# 16_Vibrationsdriver_PCA9685_1.net
KiCad netlist of a schematic drawn in EAGLE
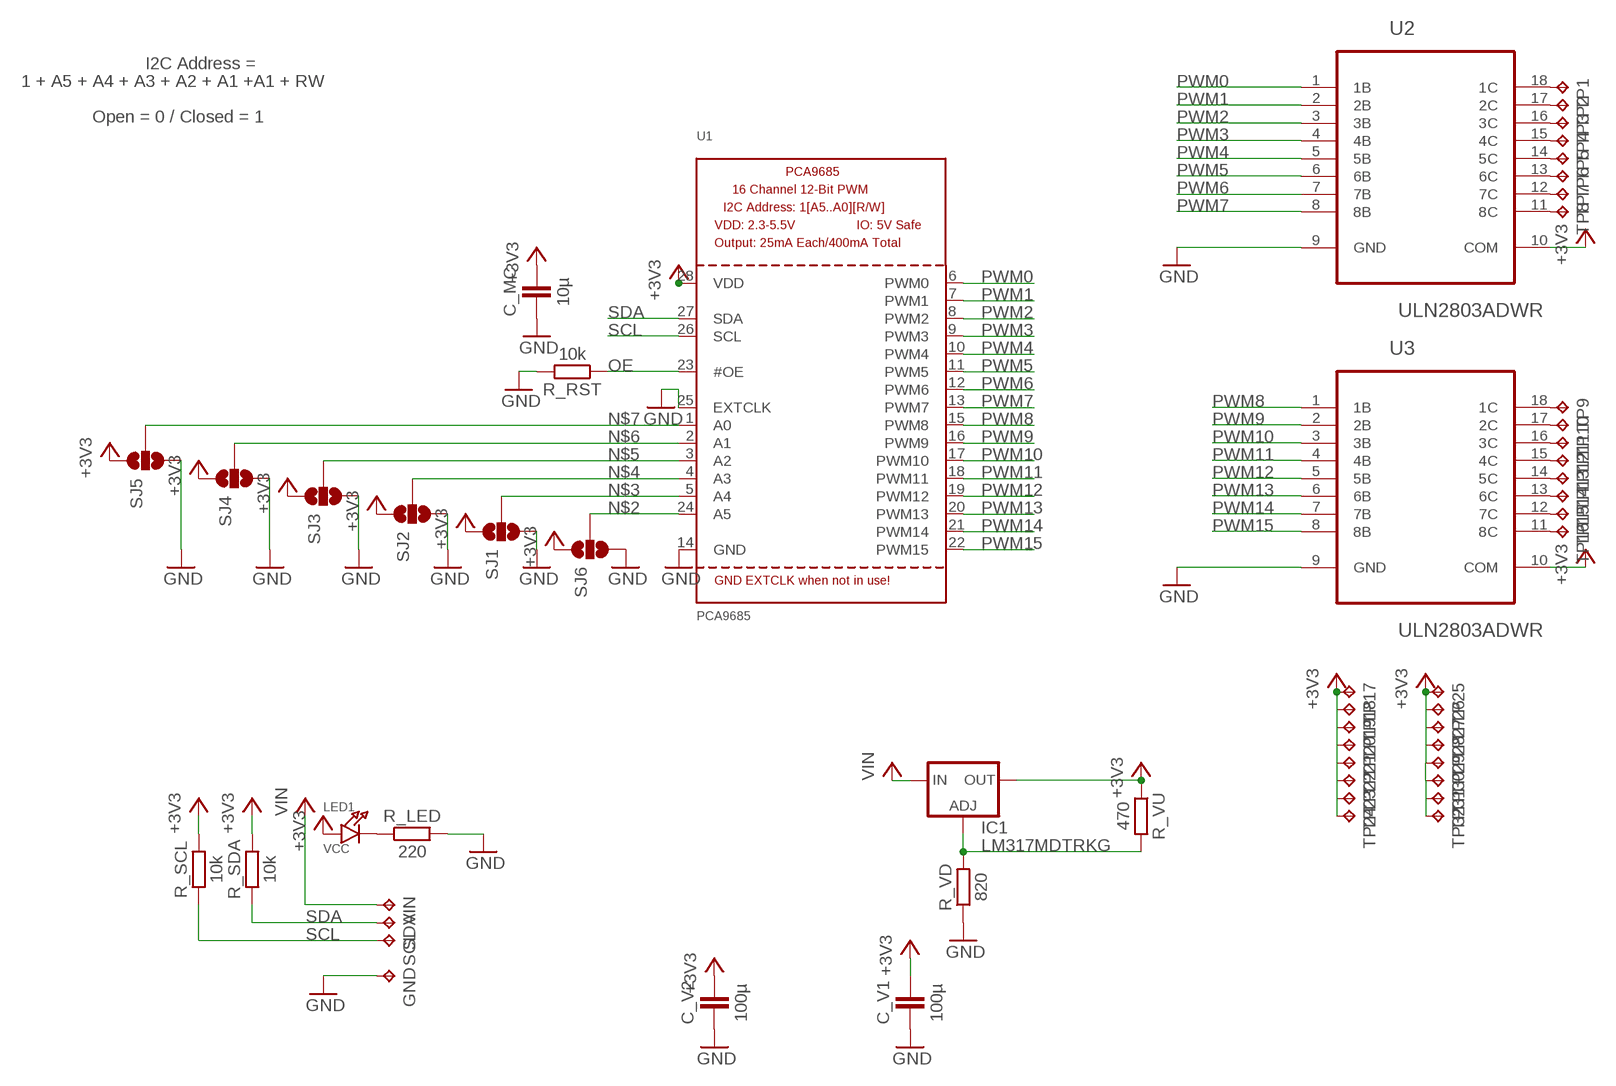
[diagram p0: schematic, sheet 1]

(export (version "E")
  (design (tool "Eeschema 10.0.6"))
  (components
    (comp (ref "C_MC")
      (value "10µ")
      (footprint "eagle-import:603")
      (libsource (lib "eagle-import") (part "CAPACITOR"))
    )
    (comp (ref "C_V1")
      (value "100µ")
      (footprint "eagle-import:1206")
      (libsource (lib "eagle-import") (part "CAPACITOR1206"))
    )
    (comp (ref "C_V2")
      (value "100µ")
      (footprint "eagle-import:1206")
      (libsource (lib "eagle-import") (part "CAPACITOR1206"))
    )
    (comp (ref "GND")
      (value "TPTP16SQ")
      (footprint "eagle-import:TP16SQ")
      (libsource (lib "eagle-import") (part "TPTP16SQ"))
    )
    (comp (ref "IC1")
      (value "LM317MDTRKG")
      (footprint "eagle-import:DPACK")
      (libsource (lib "eagle-import") (part "LM317?MDTRKG"))
    )
    (comp (ref "LED1")
      (value "VCC")
      (footprint "eagle-import:CHIPLED_0805")
      (libsource (lib "eagle-import") (part "LED0805"))
    )
    (comp (ref "R_LED")
      (value "220")
      (footprint "eagle-import:603")
      (libsource (lib "eagle-import") (part "RESISTOR0603"))
    )
    (comp (ref "R_RST")
      (value "10k")
      (footprint "eagle-import:603")
      (libsource (lib "eagle-import") (part "RESISTOR0603"))
    )
    (comp (ref "R_SCL")
      (value "10k")
      (footprint "eagle-import:603")
      (libsource (lib "eagle-import") (part "RESISTOR0603"))
    )
    (comp (ref "R_SDA")
      (value "10k")
      (footprint "eagle-import:603")
      (libsource (lib "eagle-import") (part "RESISTOR0603"))
    )
    (comp (ref "R_VD")
      (value "820")
      (footprint "eagle-import:603")
      (libsource (lib "eagle-import") (part "RESISTOR0603"))
    )
    (comp (ref "R_VU")
      (value "470")
      (footprint "eagle-import:603")
      (libsource (lib "eagle-import") (part "RESISTOR0603"))
    )
    (comp (ref "SCL")
      (value "TPTP16SQ")
      (footprint "eagle-import:TP16SQ")
      (libsource (lib "eagle-import") (part "TPTP16SQ"))
    )
    (comp (ref "SDA")
      (value "TPTP16SQ")
      (footprint "eagle-import:TP16SQ")
      (libsource (lib "eagle-import") (part "TPTP16SQ"))
    )
    (comp (ref "SJ1")
      (value "SOLDERJUMPER_2WAYPASTE2&3")
      (footprint "eagle-import:SJ_3_PASTE2&3")
      (libsource (lib "eagle-import") (part "SOLDERJUMPER_2WAYPASTE2&3"))
    )
    (comp (ref "SJ2")
      (value "SOLDERJUMPER_2WAYPASTE2&3")
      (footprint "eagle-import:SJ_3_PASTE2&3")
      (libsource (lib "eagle-import") (part "SOLDERJUMPER_2WAYPASTE2&3"))
    )
    (comp (ref "SJ3")
      (value "SOLDERJUMPER_2WAYPASTE2&3")
      (footprint "eagle-import:SJ_3_PASTE2&3")
      (libsource (lib "eagle-import") (part "SOLDERJUMPER_2WAYPASTE2&3"))
    )
    (comp (ref "SJ4")
      (value "SOLDERJUMPER_2WAYPASTE2&3")
      (footprint "eagle-import:SJ_3_PASTE2&3")
      (libsource (lib "eagle-import") (part "SOLDERJUMPER_2WAYPASTE2&3"))
    )
    (comp (ref "SJ5")
      (value "SOLDERJUMPER_2WAYPASTE2&3")
      (footprint "eagle-import:SJ_3_PASTE2&3")
      (libsource (lib "eagle-import") (part "SOLDERJUMPER_2WAYPASTE2&3"))
    )
    (comp (ref "SJ6")
      (value "SOLDERJUMPER_2WAYPASTE2&3")
      (footprint "eagle-import:SJ_3_PASTE2&3")
      (libsource (lib "eagle-import") (part "SOLDERJUMPER_2WAYPASTE2&3"))
    )
    (comp (ref "TP1")
      (value "TPTP16SQ")
      (footprint "eagle-import:TP16SQ")
      (libsource (lib "eagle-import") (part "TPTP16SQ"))
    )
    (comp (ref "TP2")
      (value "TPTP16SQ")
      (footprint "eagle-import:TP16SQ")
      (libsource (lib "eagle-import") (part "TPTP16SQ"))
    )
    (comp (ref "TP3")
      (value "TPTP16SQ")
      (footprint "eagle-import:TP16SQ")
      (libsource (lib "eagle-import") (part "TPTP16SQ"))
    )
    (comp (ref "TP4")
      (value "TPTP16SQ")
      (footprint "eagle-import:TP16SQ")
      (libsource (lib "eagle-import") (part "TPTP16SQ"))
    )
    (comp (ref "TP5")
      (value "TPTP16SQ")
      (footprint "eagle-import:TP16SQ")
      (libsource (lib "eagle-import") (part "TPTP16SQ"))
    )
    (comp (ref "TP6")
      (value "TPTP16SQ")
      (footprint "eagle-import:TP16SQ")
      (libsource (lib "eagle-import") (part "TPTP16SQ"))
    )
    (comp (ref "TP7")
      (value "TPTP16SQ")
      (footprint "eagle-import:TP16SQ")
      (libsource (lib "eagle-import") (part "TPTP16SQ"))
    )
    (comp (ref "TP8")
      (value "TPTP16SQ")
      (footprint "eagle-import:TP16SQ")
      (libsource (lib "eagle-import") (part "TPTP16SQ"))
    )
    (comp (ref "TP9")
      (value "TPTP16SQ")
      (footprint "eagle-import:TP16SQ")
      (libsource (lib "eagle-import") (part "TPTP16SQ"))
    )
    (comp (ref "TP10")
      (value "TPTP16SQ")
      (footprint "eagle-import:TP16SQ")
      (libsource (lib "eagle-import") (part "TPTP16SQ"))
    )
    (comp (ref "TP11")
      (value "TPTP16SQ")
      (footprint "eagle-import:TP16SQ")
      (libsource (lib "eagle-import") (part "TPTP16SQ"))
    )
    (comp (ref "TP12")
      (value "TPTP16SQ")
      (footprint "eagle-import:TP16SQ")
      (libsource (lib "eagle-import") (part "TPTP16SQ"))
    )
    (comp (ref "TP13")
      (value "TPTP16SQ")
      (footprint "eagle-import:TP16SQ")
      (libsource (lib "eagle-import") (part "TPTP16SQ"))
    )
    (comp (ref "TP14")
      (value "TPTP16SQ")
      (footprint "eagle-import:TP16SQ")
      (libsource (lib "eagle-import") (part "TPTP16SQ"))
    )
    (comp (ref "TP15")
      (value "TPTP16SQ")
      (footprint "eagle-import:TP16SQ")
      (libsource (lib "eagle-import") (part "TPTP16SQ"))
    )
    (comp (ref "TP16")
      (value "TPTP16SQ")
      (footprint "eagle-import:TP16SQ")
      (libsource (lib "eagle-import") (part "TPTP16SQ"))
    )
    (comp (ref "TP17")
      (value "TPTP16SQ")
      (footprint "eagle-import:TP16SQ")
      (libsource (lib "eagle-import") (part "TPTP16SQ"))
    )
    (comp (ref "TP18")
      (value "TPTP16SQ")
      (footprint "eagle-import:TP16SQ")
      (libsource (lib "eagle-import") (part "TPTP16SQ"))
    )
    (comp (ref "TP19")
      (value "TPTP16SQ")
      (footprint "eagle-import:TP16SQ")
      (libsource (lib "eagle-import") (part "TPTP16SQ"))
    )
    (comp (ref "TP20")
      (value "TPTP16SQ")
      (footprint "eagle-import:TP16SQ")
      (libsource (lib "eagle-import") (part "TPTP16SQ"))
    )
    (comp (ref "TP21")
      (value "TPTP16SQ")
      (footprint "eagle-import:TP16SQ")
      (libsource (lib "eagle-import") (part "TPTP16SQ"))
    )
    (comp (ref "TP22")
      (value "TPTP16SQ")
      (footprint "eagle-import:TP16SQ")
      (libsource (lib "eagle-import") (part "TPTP16SQ"))
    )
    (comp (ref "TP23")
      (value "TPTP16SQ")
      (footprint "eagle-import:TP16SQ")
      (libsource (lib "eagle-import") (part "TPTP16SQ"))
    )
    (comp (ref "TP24")
      (value "TPTP16SQ")
      (footprint "eagle-import:TP16SQ")
      (libsource (lib "eagle-import") (part "TPTP16SQ"))
    )
    (comp (ref "TP25")
      (value "TPTP16SQ")
      (footprint "eagle-import:TP16SQ")
      (libsource (lib "eagle-import") (part "TPTP16SQ"))
    )
    (comp (ref "TP26")
      (value "TPTP16SQ")
      (footprint "eagle-import:TP16SQ")
      (libsource (lib "eagle-import") (part "TPTP16SQ"))
    )
    (comp (ref "TP27")
      (value "TPTP16SQ")
      (footprint "eagle-import:TP16SQ")
      (libsource (lib "eagle-import") (part "TPTP16SQ"))
    )
    (comp (ref "TP28")
      (value "TPTP16SQ")
      (footprint "eagle-import:TP16SQ")
      (libsource (lib "eagle-import") (part "TPTP16SQ"))
    )
    (comp (ref "TP29")
      (value "TPTP16SQ")
      (footprint "eagle-import:TP16SQ")
      (libsource (lib "eagle-import") (part "TPTP16SQ"))
    )
    (comp (ref "TP30")
      (value "TPTP16SQ")
      (footprint "eagle-import:TP16SQ")
      (libsource (lib "eagle-import") (part "TPTP16SQ"))
    )
    (comp (ref "TP31")
      (value "TPTP16SQ")
      (footprint "eagle-import:TP16SQ")
      (libsource (lib "eagle-import") (part "TPTP16SQ"))
    )
    (comp (ref "TP32")
      (value "TPTP16SQ")
      (footprint "eagle-import:TP16SQ")
      (libsource (lib "eagle-import") (part "TPTP16SQ"))
    )
    (comp (ref "U1")
      (value "PCA9685")
      (footprint "eagle-import:TSSOP28")
      (libsource (lib "eagle-import") (part "PCA9685"))
    )
    (comp (ref "U2")
      (value "ULN2803ADWR")
      (footprint "eagle-import:SOIC127P1030X265-18N")
      (libsource (lib "eagle-import") (part "ULN2803ADWR"))
    )
    (comp (ref "U3")
      (value "ULN2803ADWR")
      (footprint "eagle-import:SOIC127P1030X265-18N")
      (libsource (lib "eagle-import") (part "ULN2803ADWR"))
    )
    (comp (ref "VIN")
      (value "TPTP16SQ")
      (footprint "eagle-import:TP16SQ")
      (libsource (lib "eagle-import") (part "TPTP16SQ"))
    )
  )
  (nets
    (net (code "1") (name "+3V3") (class "Default")
      (node (ref "C_MC") (pin "2") (pinfunction "2_2") (pintype "passive"))
      (node (ref "C_V1") (pin "2") (pinfunction "2_2") (pintype "passive"))
      (node (ref "C_V2") (pin "2") (pinfunction "2_2") (pintype "passive"))
      (node (ref "IC1") (pin "4") (pinfunction "OUT_4") (pintype "passive"))
      (node (ref "LED1") (pin "A") (pinfunction "A_A") (pintype "passive"))
      (node (ref "R_SCL") (pin "2") (pinfunction "2_2") (pintype "passive"))
      (node (ref "R_SDA") (pin "2") (pinfunction "2_2") (pintype "passive"))
      (node (ref "R_VU") (pin "1") (pinfunction "1_1") (pintype "passive"))
      (node (ref "SJ1") (pin "1") (pinfunction "1_1") (pintype "passive"))
      (node (ref "SJ2") (pin "1") (pinfunction "1_1") (pintype "passive"))
      (node (ref "SJ3") (pin "1") (pinfunction "1_1") (pintype "passive"))
      (node (ref "SJ4") (pin "1") (pinfunction "1_1") (pintype "passive"))
      (node (ref "SJ5") (pin "1") (pinfunction "1_1") (pintype "passive"))
      (node (ref "SJ6") (pin "1") (pinfunction "1_1") (pintype "passive"))
      (node (ref "TP17") (pin "TP") (pinfunction "TP_TP") (pintype "input"))
      (node (ref "TP18") (pin "TP") (pinfunction "TP_TP") (pintype "input"))
      (node (ref "TP19") (pin "TP") (pinfunction "TP_TP") (pintype "input"))
      (node (ref "TP20") (pin "TP") (pinfunction "TP_TP") (pintype "input"))
      (node (ref "TP21") (pin "TP") (pinfunction "TP_TP") (pintype "input"))
      (node (ref "TP22") (pin "TP") (pinfunction "TP_TP") (pintype "input"))
      (node (ref "TP23") (pin "TP") (pinfunction "TP_TP") (pintype "input"))
      (node (ref "TP24") (pin "TP") (pinfunction "TP_TP") (pintype "input"))
      (node (ref "TP25") (pin "TP") (pinfunction "TP_TP") (pintype "input"))
      (node (ref "TP26") (pin "TP") (pinfunction "TP_TP") (pintype "input"))
      (node (ref "TP27") (pin "TP") (pinfunction "TP_TP") (pintype "input"))
      (node (ref "TP28") (pin "TP") (pinfunction "TP_TP") (pintype "input"))
      (node (ref "TP29") (pin "TP") (pinfunction "TP_TP") (pintype "input"))
      (node (ref "TP30") (pin "TP") (pinfunction "TP_TP") (pintype "input"))
      (node (ref "TP31") (pin "TP") (pinfunction "TP_TP") (pintype "input"))
      (node (ref "TP32") (pin "TP") (pinfunction "TP_TP") (pintype "input"))
      (node (ref "U1") (pin "28") (pinfunction "VDD_28") (pintype "power_in"))
      (node (ref "U2") (pin "10") (pinfunction "COM_10") (pintype "output"))
      (node (ref "U3") (pin "10") (pinfunction "COM_10") (pintype "output"))
    )
    (net (code "2") (name "/N$2") (class "Default")
      (node (ref "SJ6") (pin "2") (pinfunction "2_2") (pintype "passive"))
      (node (ref "U1") (pin "24") (pinfunction "A5_24") (pintype "bidirectional"))
    )
    (net (code "3") (name "/N$3") (class "Default")
      (node (ref "SJ1") (pin "2") (pinfunction "2_2") (pintype "passive"))
      (node (ref "U1") (pin "5") (pinfunction "A4_5") (pintype "bidirectional"))
    )
    (net (code "4") (name "/N$4") (class "Default")
      (node (ref "SJ2") (pin "2") (pinfunction "2_2") (pintype "passive"))
      (node (ref "U1") (pin "4") (pinfunction "A3_4") (pintype "bidirectional"))
    )
    (net (code "5") (name "/N$5") (class "Default")
      (node (ref "SJ3") (pin "2") (pinfunction "2_2") (pintype "passive"))
      (node (ref "U1") (pin "3") (pinfunction "A2_3") (pintype "bidirectional"))
    )
    (net (code "6") (name "/N$6") (class "Default")
      (node (ref "SJ4") (pin "2") (pinfunction "2_2") (pintype "passive"))
      (node (ref "U1") (pin "2") (pinfunction "A1_2") (pintype "bidirectional"))
    )
    (net (code "7") (name "/N$7") (class "Default")
      (node (ref "SJ5") (pin "2") (pinfunction "2_2") (pintype "passive"))
      (node (ref "U1") (pin "1") (pinfunction "A0_1") (pintype "bidirectional"))
    )
    (net (code "8") (name "/OE") (class "Default")
      (node (ref "R_RST") (pin "1") (pinfunction "1_1") (pintype "passive"))
      (node (ref "U1") (pin "23") (pinfunction "#OE_23") (pintype "input"))
    )
    (net (code "9") (name "/PWM0") (class "Default")
      (node (ref "U1") (pin "6") (pinfunction "PWM0_6") (pintype "output"))
      (node (ref "U2") (pin "1") (pinfunction "1B_1") (pintype "input"))
    )
    (net (code "10") (name "/PWM1") (class "Default")
      (node (ref "U1") (pin "7") (pinfunction "PWM1_7") (pintype "output"))
      (node (ref "U2") (pin "2") (pinfunction "2B_2") (pintype "input"))
    )
    (net (code "11") (name "/PWM2") (class "Default")
      (node (ref "U1") (pin "8") (pinfunction "PWM2_8") (pintype "output"))
      (node (ref "U2") (pin "3") (pinfunction "3B_3") (pintype "input"))
    )
    (net (code "12") (name "/PWM3") (class "Default")
      (node (ref "U1") (pin "9") (pinfunction "PWM3_9") (pintype "output"))
      (node (ref "U2") (pin "4") (pinfunction "4B_4") (pintype "input"))
    )
    (net (code "13") (name "/PWM4") (class "Default")
      (node (ref "U1") (pin "10") (pinfunction "PWM4_10") (pintype "output"))
      (node (ref "U2") (pin "5") (pinfunction "5B_5") (pintype "input"))
    )
    (net (code "14") (name "/PWM5") (class "Default")
      (node (ref "U1") (pin "11") (pinfunction "PWM5_11") (pintype "output"))
      (node (ref "U2") (pin "6") (pinfunction "6B_6") (pintype "input"))
    )
    (net (code "15") (name "/PWM6") (class "Default")
      (node (ref "U1") (pin "12") (pinfunction "PWM6_12") (pintype "output"))
      (node (ref "U2") (pin "7") (pinfunction "7B_7") (pintype "input"))
    )
    (net (code "16") (name "/PWM7") (class "Default")
      (node (ref "U1") (pin "13") (pinfunction "PWM7_13") (pintype "output"))
      (node (ref "U2") (pin "8") (pinfunction "8B_8") (pintype "input"))
    )
    (net (code "17") (name "/PWM8") (class "Default")
      (node (ref "U1") (pin "15") (pinfunction "PWM8_15") (pintype "output"))
      (node (ref "U3") (pin "1") (pinfunction "1B_1") (pintype "input"))
    )
    (net (code "18") (name "/PWM9") (class "Default")
      (node (ref "U1") (pin "16") (pinfunction "PWM9_16") (pintype "output"))
      (node (ref "U3") (pin "2") (pinfunction "2B_2") (pintype "input"))
    )
    (net (code "19") (name "/PWM10") (class "Default")
      (node (ref "U1") (pin "17") (pinfunction "PWM10_17") (pintype "output"))
      (node (ref "U3") (pin "3") (pinfunction "3B_3") (pintype "input"))
    )
    (net (code "20") (name "/PWM11") (class "Default")
      (node (ref "U1") (pin "18") (pinfunction "PWM11_18") (pintype "output"))
      (node (ref "U3") (pin "4") (pinfunction "4B_4") (pintype "input"))
    )
    (net (code "21") (name "/PWM12") (class "Default")
      (node (ref "U1") (pin "19") (pinfunction "PWM12_19") (pintype "output"))
      (node (ref "U3") (pin "5") (pinfunction "5B_5") (pintype "input"))
    )
    (net (code "22") (name "/PWM13") (class "Default")
      (node (ref "U1") (pin "20") (pinfunction "PWM13_20") (pintype "output"))
      (node (ref "U3") (pin "6") (pinfunction "6B_6") (pintype "input"))
    )
    (net (code "23") (name "/PWM14") (class "Default")
      (node (ref "U1") (pin "21") (pinfunction "PWM14_21") (pintype "output"))
      (node (ref "U3") (pin "7") (pinfunction "7B_7") (pintype "input"))
    )
    (net (code "24") (name "/PWM15") (class "Default")
      (node (ref "U1") (pin "22") (pinfunction "PWM15_22") (pintype "output"))
      (node (ref "U3") (pin "8") (pinfunction "8B_8") (pintype "input"))
    )
    (net (code "25") (name "/SCL") (class "Default")
      (node (ref "R_SCL") (pin "1") (pinfunction "1_1") (pintype "passive"))
      (node (ref "SCL") (pin "TP") (pinfunction "TP_TP") (pintype "input"))
      (node (ref "U1") (pin "26") (pinfunction "SCL_26") (pintype "bidirectional"))
    )
    (net (code "26") (name "/SDA") (class "Default")
      (node (ref "R_SDA") (pin "1") (pinfunction "1_1") (pintype "passive"))
      (node (ref "SDA") (pin "TP") (pinfunction "TP_TP") (pintype "input"))
      (node (ref "U1") (pin "27") (pinfunction "SDA_27") (pintype "bidirectional"))
    )
    (net (code "27") (name "GND") (class "Default")
      (node (ref "C_MC") (pin "1") (pinfunction "1_1") (pintype "passive"))
      (node (ref "C_V1") (pin "1") (pinfunction "1_1") (pintype "passive"))
      (node (ref "C_V2") (pin "1") (pinfunction "1_1") (pintype "passive"))
      (node (ref "GND") (pin "TP") (pinfunction "TP_TP") (pintype "input"))
      (node (ref "R_LED") (pin "2") (pinfunction "2_2") (pintype "passive"))
      (node (ref "R_RST") (pin "2") (pinfunction "2_2") (pintype "passive"))
      (node (ref "R_VD") (pin "1") (pinfunction "1_1") (pintype "passive"))
      (node (ref "SJ1") (pin "3") (pinfunction "3_3") (pintype "passive"))
      (node (ref "SJ2") (pin "3") (pinfunction "3_3") (pintype "passive"))
      (node (ref "SJ3") (pin "3") (pinfunction "3_3") (pintype "passive"))
      (node (ref "SJ4") (pin "3") (pinfunction "3_3") (pintype "passive"))
      (node (ref "SJ5") (pin "3") (pinfunction "3_3") (pintype "passive"))
      (node (ref "SJ6") (pin "3") (pinfunction "3_3") (pintype "passive"))
      (node (ref "U1") (pin "14") (pinfunction "GND_14") (pintype "power_in"))
      (node (ref "U1") (pin "25") (pinfunction "EXTCLK_25") (pintype "input"))
      (node (ref "U2") (pin "9") (pinfunction "GND_9") (pintype "passive"))
      (node (ref "U3") (pin "9") (pinfunction "GND_9") (pintype "passive"))
    )
    (net (code "28") (name "Net-(IC1-ADJ)") (class "Default")
      (node (ref "IC1") (pin "1") (pinfunction "ADJ_1") (pintype "input"))
      (node (ref "R_VD") (pin "2") (pinfunction "2_2") (pintype "passive"))
      (node (ref "R_VU") (pin "2") (pinfunction "2_2") (pintype "passive"))
    )
    (net (code "29") (name "Net-(LED1-PadC)") (class "Default")
      (node (ref "LED1") (pin "C") (pinfunction "C_C") (pintype "passive"))
      (node (ref "R_LED") (pin "1") (pinfunction "1_1") (pintype "passive"))
    )
    (net (code "30") (name "Net-(U2-1C)") (class "Default")
      (node (ref "TP1") (pin "TP") (pinfunction "TP_TP") (pintype "input"))
      (node (ref "U2") (pin "18") (pinfunction "1C_18") (pintype "output"))
    )
    (net (code "31") (name "Net-(U2-2C)") (class "Default")
      (node (ref "TP2") (pin "TP") (pinfunction "TP_TP") (pintype "input"))
      (node (ref "U2") (pin "17") (pinfunction "2C_17") (pintype "output"))
    )
    (net (code "32") (name "Net-(U2-3C)") (class "Default")
      (node (ref "TP3") (pin "TP") (pinfunction "TP_TP") (pintype "input"))
      (node (ref "U2") (pin "16") (pinfunction "3C_16") (pintype "output"))
    )
    (net (code "33") (name "Net-(U2-4C)") (class "Default")
      (node (ref "TP4") (pin "TP") (pinfunction "TP_TP") (pintype "input"))
      (node (ref "U2") (pin "15") (pinfunction "4C_15") (pintype "output"))
    )
    (net (code "34") (name "Net-(U2-5C)") (class "Default")
      (node (ref "TP5") (pin "TP") (pinfunction "TP_TP") (pintype "input"))
      (node (ref "U2") (pin "14") (pinfunction "5C_14") (pintype "output"))
    )
    (net (code "35") (name "Net-(U2-6C)") (class "Default")
      (node (ref "TP6") (pin "TP") (pinfunction "TP_TP") (pintype "input"))
      (node (ref "U2") (pin "13") (pinfunction "6C_13") (pintype "output"))
    )
    (net (code "36") (name "Net-(U2-7C)") (class "Default")
      (node (ref "TP7") (pin "TP") (pinfunction "TP_TP") (pintype "input"))
      (node (ref "U2") (pin "12") (pinfunction "7C_12") (pintype "output"))
    )
    (net (code "37") (name "Net-(U2-8C)") (class "Default")
      (node (ref "TP8") (pin "TP") (pinfunction "TP_TP") (pintype "input"))
      (node (ref "U2") (pin "11") (pinfunction "8C_11") (pintype "output"))
    )
    (net (code "38") (name "Net-(U3-1C)") (class "Default")
      (node (ref "TP9") (pin "TP") (pinfunction "TP_TP") (pintype "input"))
      (node (ref "U3") (pin "18") (pinfunction "1C_18") (pintype "output"))
    )
    (net (code "39") (name "Net-(U3-2C)") (class "Default")
      (node (ref "TP10") (pin "TP") (pinfunction "TP_TP") (pintype "input"))
      (node (ref "U3") (pin "17") (pinfunction "2C_17") (pintype "output"))
    )
    (net (code "40") (name "Net-(U3-3C)") (class "Default")
      (node (ref "TP11") (pin "TP") (pinfunction "TP_TP") (pintype "input"))
      (node (ref "U3") (pin "16") (pinfunction "3C_16") (pintype "output"))
    )
    (net (code "41") (name "Net-(U3-4C)") (class "Default")
      (node (ref "TP12") (pin "TP") (pinfunction "TP_TP") (pintype "input"))
      (node (ref "U3") (pin "15") (pinfunction "4C_15") (pintype "output"))
    )
    (net (code "42") (name "Net-(U3-5C)") (class "Default")
      (node (ref "TP13") (pin "TP") (pinfunction "TP_TP") (pintype "input"))
      (node (ref "U3") (pin "14") (pinfunction "5C_14") (pintype "output"))
    )
    (net (code "43") (name "Net-(U3-6C)") (class "Default")
      (node (ref "TP14") (pin "TP") (pinfunction "TP_TP") (pintype "input"))
      (node (ref "U3") (pin "13") (pinfunction "6C_13") (pintype "output"))
    )
    (net (code "44") (name "Net-(U3-7C)") (class "Default")
      (node (ref "TP15") (pin "TP") (pinfunction "TP_TP") (pintype "input"))
      (node (ref "U3") (pin "12") (pinfunction "7C_12") (pintype "output"))
    )
    (net (code "45") (name "Net-(U3-8C)") (class "Default")
      (node (ref "TP16") (pin "TP") (pinfunction "TP_TP") (pintype "input"))
      (node (ref "U3") (pin "11") (pinfunction "8C_11") (pintype "output"))
    )
    (net (code "46") (name "VIN") (class "Default")
      (node (ref "IC1") (pin "3") (pinfunction "IN_3") (pintype "input"))
      (node (ref "VIN") (pin "TP") (pinfunction "TP_TP") (pintype "input"))
    )
  )
)
